# Driver6a.net
KiCad netlist of a schematic drawn in EAGLE
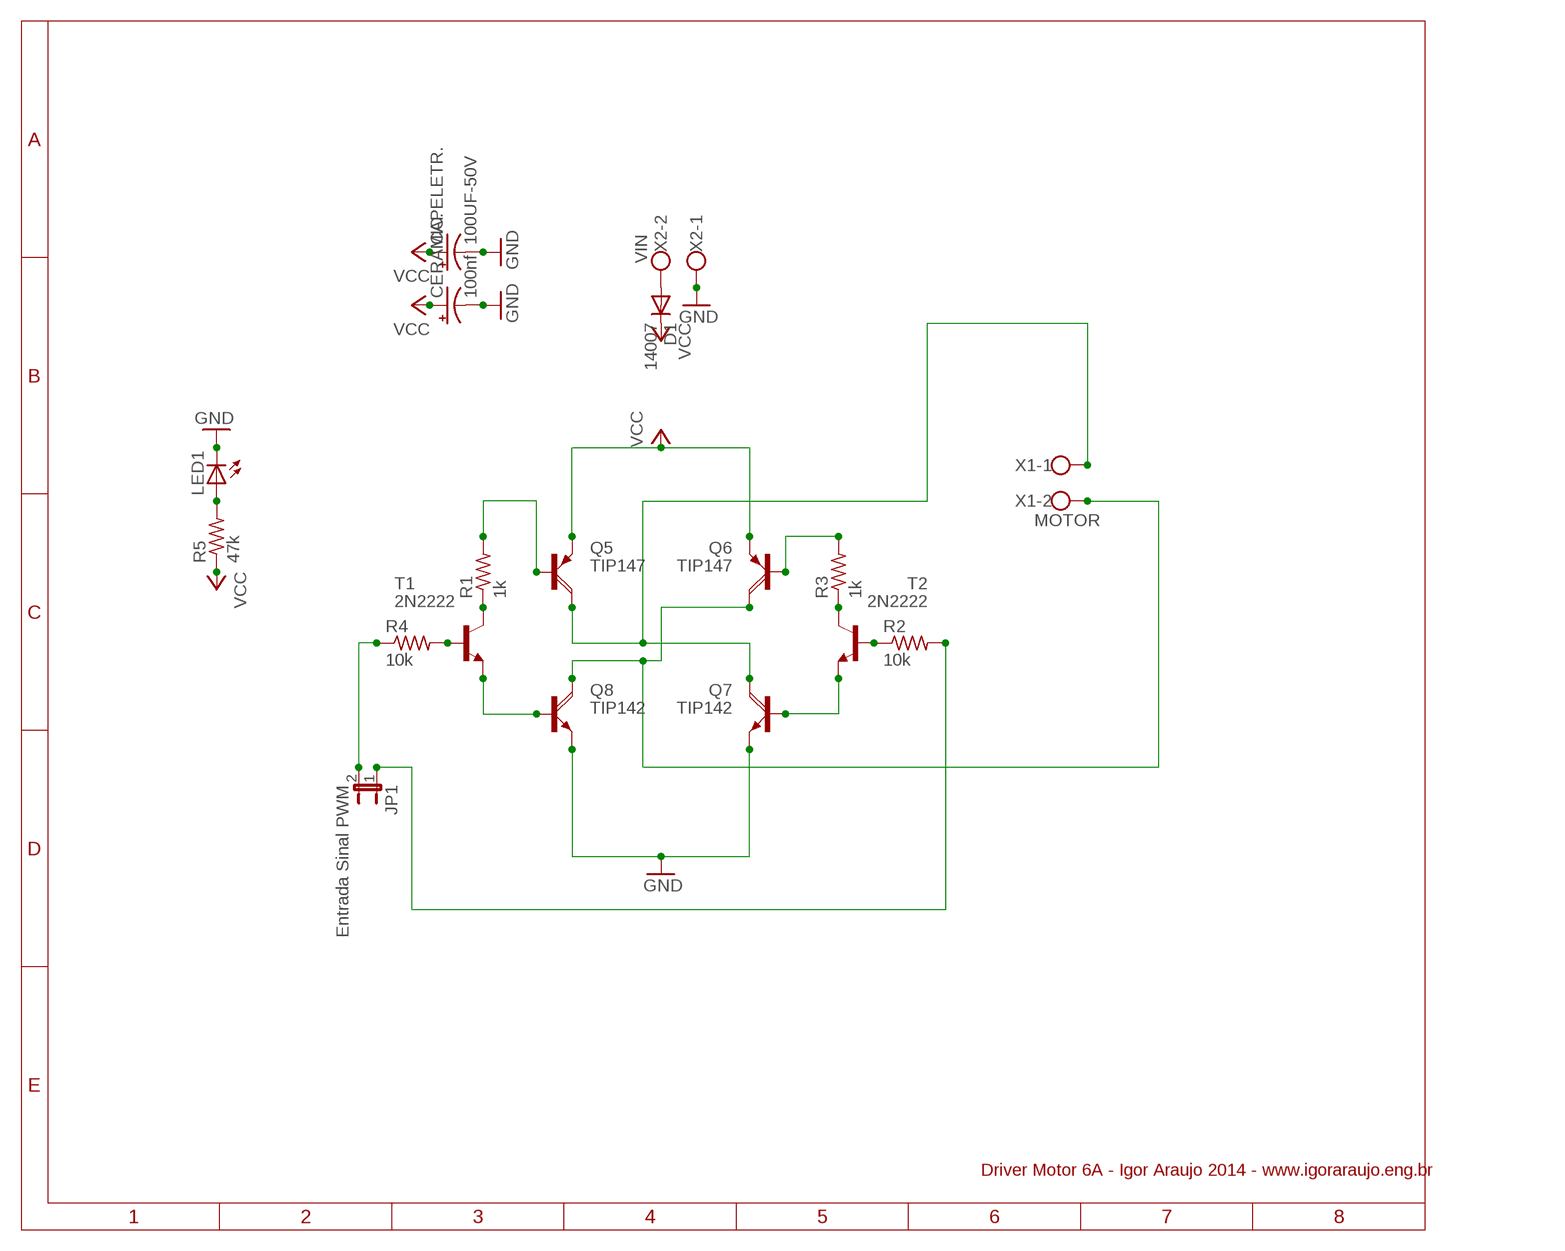
[diagram p0: schematic, sheet 1]

(export (version "E")
  (design (tool "Eeschema 10.0.6"))
  (components
    (comp (ref "CAPELETR.")
      (value "100UF-50V")
      (footprint "eagle-import:E3,5-8")
      (libsource (lib "eagle-import") (part "CPOL-USE3.5-8"))
    )
    (comp (ref "CERAMIC.")
      (value "100nf")
      (footprint "eagle-import:E3,5-8")
      (libsource (lib "eagle-import") (part "CPOL-USE3.5-8"))
    )
    (comp (ref "D1")
      (value "14007")
      (footprint "eagle-import:DO35-7")
      (libsource (lib "eagle-import") (part "1N4148DO35-7"))
    )
    (comp (ref "JP1")
      (value "Entrada Sinal PWM")
      (footprint "eagle-import:JP1")
      (libsource (lib "eagle-import") (part "JP1E"))
    )
    (comp (ref "LED1")
      (value "LED3MM")
      (footprint "eagle-import:LED3MM")
      (libsource (lib "eagle-import") (part "LED3MM"))
    )
    (comp (ref "Q5")
      (value "TIP147")
      (footprint "eagle-import:TO220AH")
      (libsource (lib "eagle-import") (part "TIP125"))
    )
    (comp (ref "Q6")
      (value "TIP147")
      (footprint "eagle-import:TO220AH")
      (libsource (lib "eagle-import") (part "TIP125"))
    )
    (comp (ref "Q7")
      (value "TIP142")
      (footprint "eagle-import:TO220AH")
      (libsource (lib "eagle-import") (part "TIP120"))
    )
    (comp (ref "Q8")
      (value "TIP142")
      (footprint "eagle-import:TO220AH")
      (libsource (lib "eagle-import") (part "TIP120"))
    )
    (comp (ref "R1")
      (value "1k")
      (footprint "eagle-import:0207_10")
      (libsource (lib "eagle-import") (part "R-US_0207/10"))
    )
    (comp (ref "R2")
      (value "10k")
      (footprint "eagle-import:0207_10")
      (libsource (lib "eagle-import") (part "R-US_0207/10"))
    )
    (comp (ref "R3")
      (value "1k")
      (footprint "eagle-import:0207_10")
      (libsource (lib "eagle-import") (part "R-US_0207/10"))
    )
    (comp (ref "R4")
      (value "10k")
      (footprint "eagle-import:0207_10")
      (libsource (lib "eagle-import") (part "R-US_0207/10"))
    )
    (comp (ref "R5")
      (value "47k")
      (footprint "eagle-import:0207_10")
      (libsource (lib "eagle-import") (part "R-US_0207/10"))
    )
    (comp (ref "T1")
      (value "2N2222")
      (footprint "eagle-import:TO18")
      (libsource (lib "eagle-import") (part "2N2222"))
    )
    (comp (ref "T2")
      (value "2N2222")
      (footprint "eagle-import:TO18")
      (libsource (lib "eagle-import") (part "2N2222"))
    )
    (comp (ref "X1")
      (value "MOTOR")
      (footprint "eagle-import:W237-132")
      (libsource (lib "eagle-import") (part "W237-02P"))
    )
    (comp (ref "X2")
      (value "VIN")
      (footprint "eagle-import:W237-132")
      (libsource (lib "eagle-import") (part "W237-02P"))
    )
  )
  (nets
    (net (code "1") (name "GND") (class "Default")
      (node (ref "CAPELETR.") (pin "-") (pinfunction "-_-") (pintype "passive"))
      (node (ref "CERAMIC.") (pin "-") (pinfunction "-_-") (pintype "passive"))
      (node (ref "LED1") (pin "K") (pinfunction "C_K") (pintype "passive"))
      (node (ref "Q7") (pin "E") (pinfunction "E_E") (pintype "passive"))
      (node (ref "Q8") (pin "E") (pinfunction "E_E") (pintype "passive"))
      (node (ref "X2") (pin "1") (pinfunction "KL_1") (pintype "passive"))
    )
    (net (code "2") (name "Net-(JP1-Pad1)") (class "Default")
      (node (ref "JP1") (pin "1") (pinfunction "1_1") (pintype "passive"))
      (node (ref "R2") (pin "2") (pinfunction "2_2") (pintype "passive"))
    )
    (net (code "3") (name "Net-(JP1-Pad2)") (class "Default")
      (node (ref "JP1") (pin "2") (pinfunction "2_2") (pintype "passive"))
      (node (ref "R4") (pin "1") (pinfunction "1_1") (pintype "passive"))
    )
    (net (code "4") (name "Net-(LED1-PadA)") (class "Default")
      (node (ref "LED1") (pin "A") (pinfunction "A_A") (pintype "passive"))
      (node (ref "R5") (pin "2") (pinfunction "2_2") (pintype "passive"))
    )
    (net (code "5") (name "Net-(Q5-PadB)") (class "Default")
      (node (ref "Q5") (pin "B") (pinfunction "B_B") (pintype "passive"))
      (node (ref "R1") (pin "2") (pinfunction "2_2") (pintype "passive"))
    )
    (net (code "6") (name "Net-(Q6-PadB)") (class "Default")
      (node (ref "Q6") (pin "B") (pinfunction "B_B") (pintype "passive"))
      (node (ref "R3") (pin "2") (pinfunction "2_2") (pintype "passive"))
    )
    (net (code "7") (name "Net-(T1-B)") (class "Default")
      (node (ref "R4") (pin "2") (pinfunction "2_2") (pintype "passive"))
      (node (ref "T1") (pin "2") (pinfunction "B_2") (pintype "passive"))
    )
    (net (code "8") (name "Net-(T1-C)") (class "Default")
      (node (ref "R1") (pin "1") (pinfunction "1_1") (pintype "passive"))
      (node (ref "T1") (pin "3") (pinfunction "C_3") (pintype "passive"))
    )
    (net (code "9") (name "Net-(T1-E)") (class "Default")
      (node (ref "Q8") (pin "B") (pinfunction "B_B") (pintype "passive"))
      (node (ref "T1") (pin "1") (pinfunction "E_1") (pintype "passive"))
    )
    (net (code "10") (name "Net-(T2-B)") (class "Default")
      (node (ref "R2") (pin "1") (pinfunction "1_1") (pintype "passive"))
      (node (ref "T2") (pin "2") (pinfunction "B_2") (pintype "passive"))
    )
    (net (code "11") (name "Net-(T2-C)") (class "Default")
      (node (ref "R3") (pin "1") (pinfunction "1_1") (pintype "passive"))
      (node (ref "T2") (pin "3") (pinfunction "C_3") (pintype "passive"))
    )
    (net (code "12") (name "Net-(T2-E)") (class "Default")
      (node (ref "Q7") (pin "B") (pinfunction "B_B") (pintype "passive"))
      (node (ref "T2") (pin "1") (pinfunction "E_1") (pintype "passive"))
    )
    (net (code "13") (name "Net-(X1A-KL)") (class "Default")
      (node (ref "Q5") (pin "C") (pinfunction "C_C") (pintype "passive"))
      (node (ref "Q7") (pin "C") (pinfunction "C_C") (pintype "passive"))
      (node (ref "X1") (pin "1") (pinfunction "KL_1") (pintype "passive"))
    )
    (net (code "14") (name "Net-(X1B-KL)") (class "Default")
      (node (ref "Q6") (pin "C") (pinfunction "C_C") (pintype "passive"))
      (node (ref "Q8") (pin "C") (pinfunction "C_C") (pintype "passive"))
      (node (ref "X1") (pin "2") (pinfunction "KL_2") (pintype "passive"))
    )
    (net (code "15") (name "Net-(X2B-KL)") (class "Default")
      (node (ref "D1") (pin "A") (pinfunction "A_A") (pintype "passive"))
      (node (ref "X2") (pin "2") (pinfunction "KL_2") (pintype "passive"))
    )
    (net (code "16") (name "VCC") (class "Default")
      (node (ref "CAPELETR.") (pin "+") (pinfunction "+_+") (pintype "passive"))
      (node (ref "CERAMIC.") (pin "+") (pinfunction "+_+") (pintype "passive"))
      (node (ref "D1") (pin "C") (pinfunction "C_C") (pintype "passive"))
      (node (ref "Q5") (pin "E") (pinfunction "E_E") (pintype "passive"))
      (node (ref "Q6") (pin "E") (pinfunction "E_E") (pintype "passive"))
      (node (ref "R5") (pin "1") (pinfunction "1_1") (pintype "passive"))
    )
  )
)
